# ADC_Temp.net
KiCad netlist of a schematic drawn in Altium Designer
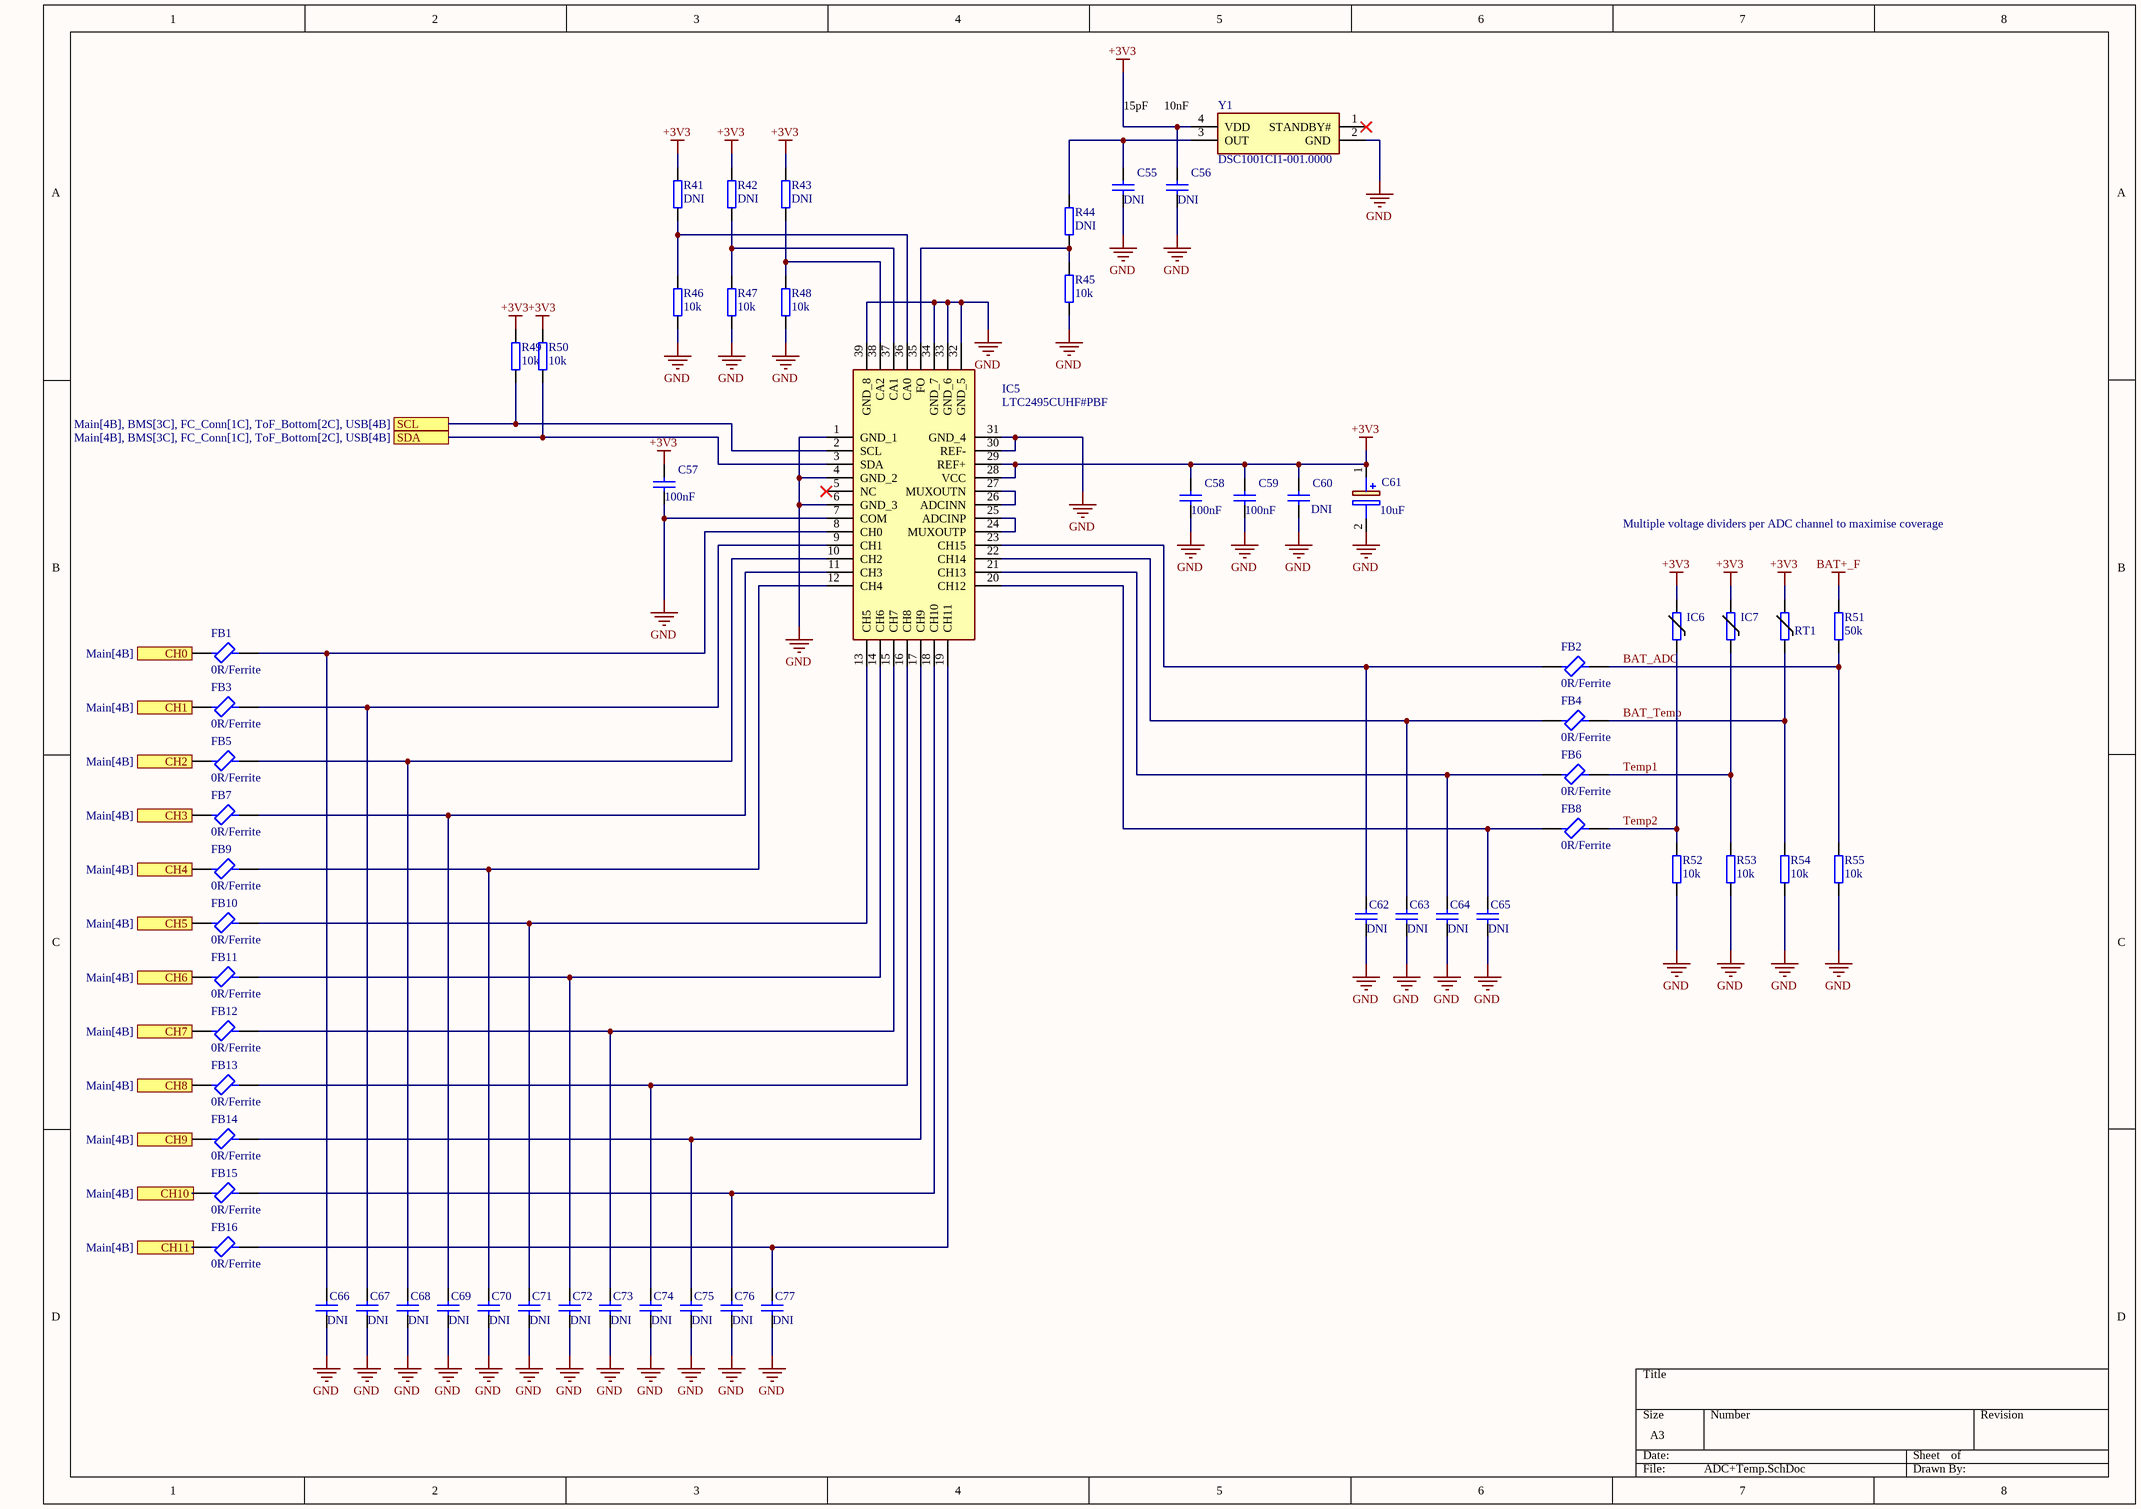
[diagram p0: ADC+Temp.SchDoc]

(export (version "E")
  (design (tool "Eeschema 10.0.6"))
  (components
    (comp (ref "C55")
      (value "DNI")
      (footprint "CAP0402")
      (fields (field (name "Comment") "Cap0402"))
      (libsource (lib "capacitorsSMD") (part "Cap0402"))
    )
    (comp (ref "C56")
      (value "DNI")
      (footprint "CAP0402")
      (fields (field (name "Comment") "Cap0402"))
      (libsource (lib "capacitorsSMD") (part "Cap0402"))
    )
    (comp (ref "C57")
      (value "100nF")
      (footprint "CAP0402")
      (fields (field (name "VOLTAGE") "50V") (field (name "Comment") "Cap0402"))
      (libsource (lib "capacitorsSMD") (part "Cap0402"))
    )
    (comp (ref "C58")
      (value "100nF")
      (footprint "CAP0402")
      (fields (field (name "VOLTAGE") "50V") (field (name "Comment") "Cap0402"))
      (libsource (lib "capacitorsSMD") (part "Cap0402"))
    )
    (comp (ref "C59")
      (value "100nF")
      (footprint "CAP0402")
      (fields (field (name "VOLTAGE") "50V") (field (name "Comment") "Cap0402"))
      (libsource (lib "capacitorsSMD") (part "Cap0402"))
    )
    (comp (ref "C60")
      (value "DNI")
      (footprint "CAP0603")
      (fields (field (name "Comment") "Cap0603"))
      (libsource (lib "capacitorsSMD") (part "Cap0603"))
    )
    (comp (ref "C61")
      (value "10uF")
      (footprint "SamacSys:CAPPC1608X90N")
      (description "Capacitor Polarised")
      (fields (field (name "VOLTAGE") "6V3") (field (name "Comment") "TMCJ0J106MTRF"))
      (libsource (lib "*") (part "298D106X96R3M2T"))
    )
    (comp (ref "C62")
      (value "DNI")
      (footprint "CAP0402")
      (fields (field (name "Comment") "Cap0402"))
      (libsource (lib "capacitorsSMD") (part "Cap0402"))
    )
    (comp (ref "C63")
      (value "DNI")
      (footprint "CAP0402")
      (fields (field (name "Comment") "Cap0402"))
      (libsource (lib "capacitorsSMD") (part "Cap0402"))
    )
    (comp (ref "C64")
      (value "DNI")
      (footprint "CAP0402")
      (fields (field (name "Comment") "Cap0402"))
      (libsource (lib "capacitorsSMD") (part "Cap0402"))
    )
    (comp (ref "C65")
      (value "DNI")
      (footprint "CAP0402")
      (fields (field (name "Comment") "Cap0402"))
      (libsource (lib "capacitorsSMD") (part "Cap0402"))
    )
    (comp (ref "C66")
      (value "DNI")
      (footprint "CAP0402")
      (fields (field (name "Comment") "Cap0402"))
      (libsource (lib "capacitorsSMD") (part "Cap0402"))
    )
    (comp (ref "C67")
      (value "DNI")
      (footprint "CAP0402")
      (fields (field (name "Comment") "Cap0402"))
      (libsource (lib "capacitorsSMD") (part "Cap0402"))
    )
    (comp (ref "C68")
      (value "DNI")
      (footprint "CAP0402")
      (fields (field (name "Comment") "Cap0402"))
      (libsource (lib "capacitorsSMD") (part "Cap0402"))
    )
    (comp (ref "C69")
      (value "DNI")
      (footprint "CAP0402")
      (fields (field (name "Comment") "Cap0402"))
      (libsource (lib "capacitorsSMD") (part "Cap0402"))
    )
    (comp (ref "C70")
      (value "DNI")
      (footprint "CAP0402")
      (fields (field (name "Comment") "Cap0402"))
      (libsource (lib "capacitorsSMD") (part "Cap0402"))
    )
    (comp (ref "C71")
      (value "DNI")
      (footprint "CAP0402")
      (fields (field (name "Comment") "Cap0402"))
      (libsource (lib "capacitorsSMD") (part "Cap0402"))
    )
    (comp (ref "C72")
      (value "DNI")
      (footprint "CAP0402")
      (fields (field (name "Comment") "Cap0402"))
      (libsource (lib "capacitorsSMD") (part "Cap0402"))
    )
    (comp (ref "C73")
      (value "DNI")
      (footprint "CAP0402")
      (fields (field (name "Comment") "Cap0402"))
      (libsource (lib "capacitorsSMD") (part "Cap0402"))
    )
    (comp (ref "C74")
      (value "DNI")
      (footprint "CAP0402")
      (fields (field (name "Comment") "Cap0402"))
      (libsource (lib "capacitorsSMD") (part "Cap0402"))
    )
    (comp (ref "C75")
      (value "DNI")
      (footprint "CAP0402")
      (fields (field (name "Comment") "Cap0402"))
      (libsource (lib "capacitorsSMD") (part "Cap0402"))
    )
    (comp (ref "C76")
      (value "DNI")
      (footprint "CAP0402")
      (fields (field (name "Comment") "Cap0402"))
      (libsource (lib "capacitorsSMD") (part "Cap0402"))
    )
    (comp (ref "C77")
      (value "DNI")
      (footprint "CAP0402")
      (fields (field (name "Comment") "Cap0402"))
      (libsource (lib "capacitorsSMD") (part "Cap0402"))
    )
    (comp (ref "FB1")
      (value "0R/Ferrite")
      (footprint "SamacSys:NFZ15SG152SN10B")
      (description "Ferrite Bead")
      (fields
        (field (name "MANUFACTURER_PART_NUMBER") "BLM15PE471SH1D")
        (field (name "MOUSER PART NUMBER") "81-BLM15PE471SH1D")
      )
      (libsource (lib "SamacSys") (part "BLM15PE471SH1D"))
    )
    (comp (ref "FB2")
      (value "0R/Ferrite")
      (footprint "SamacSys:NFZ15SG152SN10B")
      (description "Ferrite Bead")
      (fields
        (field (name "MANUFACTURER_PART_NUMBER") "BLM15PE471SH1D")
        (field (name "MOUSER PART NUMBER") "81-BLM15PE471SH1D")
      )
      (libsource (lib "SamacSys") (part "BLM15PE471SH1D"))
    )
    (comp (ref "FB3")
      (value "0R/Ferrite")
      (footprint "SamacSys:NFZ15SG152SN10B")
      (description "Ferrite Bead")
      (fields
        (field (name "MANUFACTURER_PART_NUMBER") "BLM15PE471SH1D")
        (field (name "MOUSER PART NUMBER") "81-BLM15PE471SH1D")
      )
      (libsource (lib "SamacSys") (part "BLM15PE471SH1D"))
    )
    (comp (ref "FB4")
      (value "0R/Ferrite")
      (footprint "SamacSys:NFZ15SG152SN10B")
      (description "Ferrite Bead")
      (fields
        (field (name "MANUFACTURER_PART_NUMBER") "BLM15PE471SH1D")
        (field (name "MOUSER PART NUMBER") "81-BLM15PE471SH1D")
      )
      (libsource (lib "SamacSys") (part "BLM15PE471SH1D"))
    )
    (comp (ref "FB5")
      (value "0R/Ferrite")
      (footprint "SamacSys:NFZ15SG152SN10B")
      (description "Ferrite Bead")
      (fields
        (field (name "MANUFACTURER_PART_NUMBER") "BLM15PE471SH1D")
        (field (name "MOUSER PART NUMBER") "81-BLM15PE471SH1D")
      )
      (libsource (lib "SamacSys") (part "BLM15PE471SH1D"))
    )
    (comp (ref "FB6")
      (value "0R/Ferrite")
      (footprint "SamacSys:NFZ15SG152SN10B")
      (description "Ferrite Bead")
      (fields
        (field (name "MANUFACTURER_PART_NUMBER") "BLM15PE471SH1D")
        (field (name "MOUSER PART NUMBER") "81-BLM15PE471SH1D")
      )
      (libsource (lib "SamacSys") (part "BLM15PE471SH1D"))
    )
    (comp (ref "FB7")
      (value "0R/Ferrite")
      (footprint "SamacSys:NFZ15SG152SN10B")
      (description "Ferrite Bead")
      (fields
        (field (name "MANUFACTURER_PART_NUMBER") "BLM15PE471SH1D")
        (field (name "MOUSER PART NUMBER") "81-BLM15PE471SH1D")
      )
      (libsource (lib "SamacSys") (part "BLM15PE471SH1D"))
    )
    (comp (ref "FB8")
      (value "0R/Ferrite")
      (footprint "SamacSys:NFZ15SG152SN10B")
      (description "Ferrite Bead")
      (fields
        (field (name "MANUFACTURER_PART_NUMBER") "BLM15PE471SH1D")
        (field (name "MOUSER PART NUMBER") "81-BLM15PE471SH1D")
      )
      (libsource (lib "SamacSys") (part "BLM15PE471SH1D"))
    )
    (comp (ref "FB9")
      (value "0R/Ferrite")
      (footprint "SamacSys:NFZ15SG152SN10B")
      (description "Ferrite Bead")
      (fields
        (field (name "MANUFACTURER_PART_NUMBER") "BLM15PE471SH1D")
        (field (name "MOUSER PART NUMBER") "81-BLM15PE471SH1D")
      )
      (libsource (lib "SamacSys") (part "BLM15PE471SH1D"))
    )
    (comp (ref "FB10")
      (value "0R/Ferrite")
      (footprint "SamacSys:NFZ15SG152SN10B")
      (description "Ferrite Bead")
      (fields
        (field (name "MANUFACTURER_PART_NUMBER") "BLM15PE471SH1D")
        (field (name "MOUSER PART NUMBER") "81-BLM15PE471SH1D")
      )
      (libsource (lib "SamacSys") (part "BLM15PE471SH1D"))
    )
    (comp (ref "FB11")
      (value "0R/Ferrite")
      (footprint "SamacSys:NFZ15SG152SN10B")
      (description "Ferrite Bead")
      (fields
        (field (name "MANUFACTURER_PART_NUMBER") "BLM15PE471SH1D")
        (field (name "MOUSER PART NUMBER") "81-BLM15PE471SH1D")
      )
      (libsource (lib "SamacSys") (part "BLM15PE471SH1D"))
    )
    (comp (ref "FB12")
      (value "0R/Ferrite")
      (footprint "SamacSys:NFZ15SG152SN10B")
      (description "Ferrite Bead")
      (fields
        (field (name "MANUFACTURER_PART_NUMBER") "BLM15PE471SH1D")
        (field (name "MOUSER PART NUMBER") "81-BLM15PE471SH1D")
      )
      (libsource (lib "SamacSys") (part "BLM15PE471SH1D"))
    )
    (comp (ref "FB13")
      (value "0R/Ferrite")
      (footprint "SamacSys:NFZ15SG152SN10B")
      (description "Ferrite Bead")
      (fields
        (field (name "MANUFACTURER_PART_NUMBER") "BLM15PE471SH1D")
        (field (name "MOUSER PART NUMBER") "81-BLM15PE471SH1D")
      )
      (libsource (lib "SamacSys") (part "BLM15PE471SH1D"))
    )
    (comp (ref "FB14")
      (value "0R/Ferrite")
      (footprint "SamacSys:NFZ15SG152SN10B")
      (description "Ferrite Bead")
      (fields
        (field (name "MANUFACTURER_PART_NUMBER") "BLM15PE471SH1D")
        (field (name "MOUSER PART NUMBER") "81-BLM15PE471SH1D")
      )
      (libsource (lib "SamacSys") (part "BLM15PE471SH1D"))
    )
    (comp (ref "FB15")
      (value "0R/Ferrite")
      (footprint "SamacSys:NFZ15SG152SN10B")
      (description "Ferrite Bead")
      (fields
        (field (name "MANUFACTURER_PART_NUMBER") "BLM15PE471SH1D")
        (field (name "MOUSER PART NUMBER") "81-BLM15PE471SH1D")
      )
      (libsource (lib "SamacSys") (part "BLM15PE471SH1D"))
    )
    (comp (ref "FB16")
      (value "0R/Ferrite")
      (footprint "SamacSys:NFZ15SG152SN10B")
      (description "Ferrite Bead")
      (fields
        (field (name "MANUFACTURER_PART_NUMBER") "BLM15PE471SH1D")
        (field (name "MOUSER PART NUMBER") "81-BLM15PE471SH1D")
      )
      (libsource (lib "SamacSys") (part "BLM15PE471SH1D"))
    )
    (comp (ref "IC5")
      (value "LTC2495CUHF#PBF")
      (footprint "SamacSys:QFN50P500X700X80-39N-D")
      (description "Integrated Circuit")
      (fields (field (name "MOUSER PART NUMBER") "584-LTC2495CUHF#PBF"))
      (libsource (lib "*") (part "LTC2495CUHF#PBF"))
    )
    (comp (ref "IC6")
      (value "TMP6131DECR")
      (footprint "SamacSys:TMP6131DECR")
      (description "Integrated Circuit")
      (fields (field (name "MOUSER PART NUMBER") "595-TMP6131DECR"))
      (libsource (lib "SamacSys") (part "TMP6131DECR"))
    )
    (comp (ref "IC7")
      (value "TMP6131DECR")
      (footprint "SamacSys:TMP6131DECR")
      (description "Integrated Circuit")
      (fields (field (name "MOUSER PART NUMBER") "595-TMP6131DECR"))
      (libsource (lib "SamacSys") (part "TMP6131DECR"))
    )
    (comp (ref "R41")
      (value "DNI")
      (footprint "RES0402")
      (fields (field (name "Comment") "Res0402"))
      (libsource (lib "resistorSMD") (part "Res0402"))
    )
    (comp (ref "R42")
      (value "DNI")
      (footprint "RES0402")
      (fields (field (name "Comment") "Res0402"))
      (libsource (lib "resistorSMD") (part "Res0402"))
    )
    (comp (ref "R43")
      (value "DNI")
      (footprint "RES0402")
      (fields (field (name "Comment") "Res0402"))
      (libsource (lib "resistorSMD") (part "Res0402"))
    )
    (comp (ref "R44")
      (value "DNI")
      (footprint "RES0402")
      (fields (field (name "Comment") "Res0402"))
      (libsource (lib "resistorSMD") (part "Res0402"))
    )
    (comp (ref "R45")
      (value "10k")
      (footprint "RES0402")
      (fields (field (name "Comment") "Res0402"))
      (libsource (lib "resistorSMD") (part "Res0402"))
    )
    (comp (ref "R46")
      (value "10k")
      (footprint "RES0402")
      (fields (field (name "Comment") "Res0402"))
      (libsource (lib "resistorSMD") (part "Res0402"))
    )
    (comp (ref "R47")
      (value "10k")
      (footprint "RES0402")
      (fields (field (name "Comment") "Res0402"))
      (libsource (lib "resistorSMD") (part "Res0402"))
    )
    (comp (ref "R48")
      (value "10k")
      (footprint "RES0402")
      (fields (field (name "Comment") "Res0402"))
      (libsource (lib "resistorSMD") (part "Res0402"))
    )
    (comp (ref "R49")
      (value "10k")
      (footprint "RES0402")
      (fields (field (name "Comment") "Res0402"))
      (libsource (lib "resistorSMD") (part "Res0402"))
    )
    (comp (ref "R50")
      (value "10k")
      (footprint "RES0402")
      (fields (field (name "Comment") "Res0402"))
      (libsource (lib "resistorSMD") (part "Res0402"))
    )
    (comp (ref "R51")
      (value "50k")
      (footprint "RES0402")
      (fields (field (name "Comment") "Res0402"))
      (libsource (lib "resistorSMD") (part "Res0402"))
    )
    (comp (ref "R52")
      (value "10k")
      (footprint "RES0402")
      (fields (field (name "Comment") "Res0402"))
      (libsource (lib "resistorSMD") (part "Res0402"))
    )
    (comp (ref "R53")
      (value "10k")
      (footprint "RES0402")
      (fields (field (name "Comment") "Res0402"))
      (libsource (lib "resistorSMD") (part "Res0402"))
    )
    (comp (ref "R54")
      (value "10k")
      (footprint "RES0402")
      (fields (field (name "Comment") "Res0402"))
      (libsource (lib "resistorSMD") (part "Res0402"))
    )
    (comp (ref "R55")
      (value "10k")
      (footprint "RES0402")
      (fields (field (name "Comment") "Res0402"))
      (libsource (lib "resistorSMD") (part "Res0402"))
    )
    (comp (ref "RT1")
      (value "B57862L0103F000/B59100M1080A070")
      (footprint "SamacSys:B57862L0102F000")
      (description "Thermistor")
      (fields
        (field (name "MANUFACTURER_PART_NUMBER") "B57862L0103F000")
        (field (name "MOUSER PART NUMBER") "871-B57862L0103F000")
      )
      (libsource (lib "SamacSys") (part "B57862L0103F000"))
    )
    (comp (ref "Y1")
      (value "DSC1001CI1-001.0000")
      (footprint "SamacSys:DSC1001CI10010000")
      (description "DNI")
      (fields (field (name "MOUSER PART NUMBER") "998-1001CI1-001.0000"))
      (libsource (lib "*") (part "DSC1001CI1-001.0000"))
    )
  )
  (nets
    (net (code "1") (name "+3V3") (class "Default")
      (node (ref "C56") (pin "2") (pinfunction "2_2") (pintype "passive"))
      (node (ref "C57") (pin "2") (pinfunction "2_2") (pintype "passive"))
      (node (ref "C58") (pin "2") (pinfunction "2_2") (pintype "passive"))
      (node (ref "C59") (pin "2") (pinfunction "2_2") (pintype "passive"))
      (node (ref "C60") (pin "2") (pinfunction "2_2") (pintype "passive"))
      (node (ref "C61") (pin "1") (pinfunction "+_1") (pintype "passive"))
      (node (ref "IC5") (pin "28") (pinfunction "VCC_28") (pintype "passive"))
      (node (ref "IC5") (pin "29") (pinfunction "REF+_29") (pintype "passive"))
      (node (ref "IC6") (pin "2") (pinfunction "2_2") (pintype "passive"))
      (node (ref "IC7") (pin "2") (pinfunction "2_2") (pintype "passive"))
      (node (ref "R41") (pin "2") (pinfunction "2_2") (pintype "passive"))
      (node (ref "R42") (pin "2") (pinfunction "2_2") (pintype "passive"))
      (node (ref "R43") (pin "2") (pinfunction "2_2") (pintype "passive"))
      (node (ref "R49") (pin "2") (pinfunction "2_2") (pintype "passive"))
      (node (ref "R50") (pin "2") (pinfunction "2_2") (pintype "passive"))
      (node (ref "RT1") (pin "2") (pinfunction "2_2") (pintype "passive"))
      (node (ref "Y1") (pin "4") (pinfunction "VDD_4") (pintype "passive"))
    )
    (net (code "2") (name "/BAT_ADC") (class "Default")
      (node (ref "FB2") (pin "2") (pinfunction "2_2") (pintype "passive"))
      (node (ref "R51") (pin "1") (pinfunction "1_1") (pintype "passive"))
      (node (ref "R55") (pin "2") (pinfunction "2_2") (pintype "passive"))
    )
    (net (code "3") (name "/BAT_Temp") (class "Default")
      (node (ref "FB4") (pin "2") (pinfunction "2_2") (pintype "passive"))
      (node (ref "R54") (pin "2") (pinfunction "2_2") (pintype "passive"))
      (node (ref "RT1") (pin "1") (pinfunction "1_1") (pintype "passive"))
    )
    (net (code "4") (name "/CH0") (class "Default")
      (node (ref "FB1") (pin "1") (pinfunction "1_1") (pintype "passive"))
    )
    (net (code "5") (name "/CH1") (class "Default")
      (node (ref "FB3") (pin "1") (pinfunction "1_1") (pintype "passive"))
    )
    (net (code "6") (name "/CH2") (class "Default")
      (node (ref "FB5") (pin "1") (pinfunction "1_1") (pintype "passive"))
    )
    (net (code "7") (name "/CH3") (class "Default")
      (node (ref "FB7") (pin "1") (pinfunction "1_1") (pintype "passive"))
    )
    (net (code "8") (name "/CH4") (class "Default")
      (node (ref "FB9") (pin "1") (pinfunction "1_1") (pintype "passive"))
    )
    (net (code "9") (name "/CH5") (class "Default")
      (node (ref "FB10") (pin "1") (pinfunction "1_1") (pintype "passive"))
    )
    (net (code "10") (name "/CH6") (class "Default")
      (node (ref "FB11") (pin "1") (pinfunction "1_1") (pintype "passive"))
    )
    (net (code "11") (name "/CH7") (class "Default")
      (node (ref "FB12") (pin "1") (pinfunction "1_1") (pintype "passive"))
    )
    (net (code "12") (name "/CH8") (class "Default")
      (node (ref "FB13") (pin "1") (pinfunction "1_1") (pintype "passive"))
    )
    (net (code "13") (name "/CH9") (class "Default")
      (node (ref "FB14") (pin "1") (pinfunction "1_1") (pintype "passive"))
    )
    (net (code "14") (name "/CH10") (class "Default")
      (node (ref "FB15") (pin "1") (pinfunction "1_1") (pintype "passive"))
    )
    (net (code "15") (name "/CH11") (class "Default")
      (node (ref "FB16") (pin "1") (pinfunction "1_1") (pintype "passive"))
    )
    (net (code "16") (name "/SCL") (class "Default")
      (node (ref "IC5") (pin "2") (pinfunction "SCL_2") (pintype "passive"))
      (node (ref "R49") (pin "1") (pinfunction "1_1") (pintype "passive"))
    )
    (net (code "17") (name "/SDA") (class "Default")
      (node (ref "IC5") (pin "3") (pinfunction "SDA_3") (pintype "passive"))
      (node (ref "R50") (pin "1") (pinfunction "1_1") (pintype "passive"))
    )
    (net (code "18") (name "/Temp1") (class "Default")
      (node (ref "FB6") (pin "2") (pinfunction "2_2") (pintype "passive"))
      (node (ref "IC7") (pin "1") (pinfunction "1_1") (pintype "passive"))
      (node (ref "R53") (pin "2") (pinfunction "2_2") (pintype "passive"))
    )
    (net (code "19") (name "/Temp2") (class "Default")
      (node (ref "FB8") (pin "2") (pinfunction "2_2") (pintype "passive"))
      (node (ref "IC6") (pin "1") (pinfunction "1_1") (pintype "passive"))
      (node (ref "R52") (pin "2") (pinfunction "2_2") (pintype "passive"))
    )
    (net (code "20") (name "BAT+_F") (class "Default")
      (node (ref "R51") (pin "2") (pinfunction "2_2") (pintype "passive"))
    )
    (net (code "21") (name "GND") (class "Default")
      (node (ref "C55") (pin "1") (pinfunction "1_1") (pintype "passive"))
      (node (ref "C56") (pin "1") (pinfunction "1_1") (pintype "passive"))
      (node (ref "C57") (pin "1") (pinfunction "1_1") (pintype "passive"))
      (node (ref "C58") (pin "1") (pinfunction "1_1") (pintype "passive"))
      (node (ref "C59") (pin "1") (pinfunction "1_1") (pintype "passive"))
      (node (ref "C60") (pin "1") (pinfunction "1_1") (pintype "passive"))
      (node (ref "C61") (pin "2") (pinfunction "-_2") (pintype "passive"))
      (node (ref "C62") (pin "1") (pinfunction "1_1") (pintype "passive"))
      (node (ref "C63") (pin "1") (pinfunction "1_1") (pintype "passive"))
      (node (ref "C64") (pin "1") (pinfunction "1_1") (pintype "passive"))
      (node (ref "C65") (pin "1") (pinfunction "1_1") (pintype "passive"))
      (node (ref "C66") (pin "1") (pinfunction "1_1") (pintype "passive"))
      (node (ref "C67") (pin "1") (pinfunction "1_1") (pintype "passive"))
      (node (ref "C68") (pin "1") (pinfunction "1_1") (pintype "passive"))
      (node (ref "C69") (pin "1") (pinfunction "1_1") (pintype "passive"))
      (node (ref "C70") (pin "1") (pinfunction "1_1") (pintype "passive"))
      (node (ref "C71") (pin "1") (pinfunction "1_1") (pintype "passive"))
      (node (ref "C72") (pin "1") (pinfunction "1_1") (pintype "passive"))
      (node (ref "C73") (pin "1") (pinfunction "1_1") (pintype "passive"))
      (node (ref "C74") (pin "1") (pinfunction "1_1") (pintype "passive"))
      (node (ref "C75") (pin "1") (pinfunction "1_1") (pintype "passive"))
      (node (ref "C76") (pin "1") (pinfunction "1_1") (pintype "passive"))
      (node (ref "C77") (pin "1") (pinfunction "1_1") (pintype "passive"))
      (node (ref "IC5") (pin "1") (pinfunction "GND_1_1") (pintype "passive"))
      (node (ref "IC5") (pin "30") (pinfunction "REF-_30") (pintype "passive"))
      (node (ref "IC5") (pin "31") (pinfunction "GND_4_31") (pintype "passive"))
      (node (ref "IC5") (pin "32") (pinfunction "GND_5_32") (pintype "passive"))
      (node (ref "IC5") (pin "33") (pinfunction "GND_6_33") (pintype "passive"))
      (node (ref "IC5") (pin "34") (pinfunction "GND_7_34") (pintype "passive"))
      (node (ref "IC5") (pin "39") (pinfunction "GND_8_39") (pintype "passive"))
      (node (ref "IC5") (pin "4") (pinfunction "GND_2_4") (pintype "passive"))
      (node (ref "IC5") (pin "6") (pinfunction "GND_3_6") (pintype "passive"))
      (node (ref "IC5") (pin "7") (pinfunction "COM_7") (pintype "passive"))
      (node (ref "R45") (pin "1") (pinfunction "1_1") (pintype "passive"))
      (node (ref "R46") (pin "1") (pinfunction "1_1") (pintype "passive"))
      (node (ref "R47") (pin "1") (pinfunction "1_1") (pintype "passive"))
      (node (ref "R48") (pin "1") (pinfunction "1_1") (pintype "passive"))
      (node (ref "R52") (pin "1") (pinfunction "1_1") (pintype "passive"))
      (node (ref "R53") (pin "1") (pinfunction "1_1") (pintype "passive"))
      (node (ref "R54") (pin "1") (pinfunction "1_1") (pintype "passive"))
      (node (ref "R55") (pin "1") (pinfunction "1_1") (pintype "passive"))
      (node (ref "Y1") (pin "2") (pinfunction "GND_2") (pintype "passive"))
    )
    (net (code "22") (name "Net-(IC5-ADCINN)") (class "Default")
      (node (ref "IC5") (pin "26") (pinfunction "ADCINN_26") (pintype "passive"))
      (node (ref "IC5") (pin "27") (pinfunction "MUXOUTN_27") (pintype "passive"))
    )
    (net (code "23") (name "Net-(IC5-ADCINP)") (class "Default")
      (node (ref "IC5") (pin "24") (pinfunction "MUXOUTP_24") (pintype "passive"))
      (node (ref "IC5") (pin "25") (pinfunction "ADCINP_25") (pintype "passive"))
    )
    (net (code "24") (name "Net-(IC5-CA0)") (class "Default")
      (node (ref "IC5") (pin "36") (pinfunction "CA0_36") (pintype "passive"))
      (node (ref "R41") (pin "1") (pinfunction "1_1") (pintype "passive"))
      (node (ref "R46") (pin "2") (pinfunction "2_2") (pintype "passive"))
    )
    (net (code "25") (name "Net-(IC5-CA1)") (class "Default")
      (node (ref "IC5") (pin "37") (pinfunction "CA1_37") (pintype "passive"))
      (node (ref "R42") (pin "1") (pinfunction "1_1") (pintype "passive"))
      (node (ref "R47") (pin "2") (pinfunction "2_2") (pintype "passive"))
    )
    (net (code "26") (name "Net-(IC5-CA2)") (class "Default")
      (node (ref "IC5") (pin "38") (pinfunction "CA2_38") (pintype "passive"))
      (node (ref "R43") (pin "1") (pinfunction "1_1") (pintype "passive"))
      (node (ref "R48") (pin "2") (pinfunction "2_2") (pintype "passive"))
    )
    (net (code "27") (name "Net-(IC5-CH0)") (class "Default")
      (node (ref "C66") (pin "2") (pinfunction "2_2") (pintype "passive"))
      (node (ref "FB1") (pin "2") (pinfunction "2_2") (pintype "passive"))
      (node (ref "IC5") (pin "8") (pinfunction "CH0_8") (pintype "passive"))
    )
    (net (code "28") (name "Net-(IC5-CH1)") (class "Default")
      (node (ref "C67") (pin "2") (pinfunction "2_2") (pintype "passive"))
      (node (ref "FB3") (pin "2") (pinfunction "2_2") (pintype "passive"))
      (node (ref "IC5") (pin "9") (pinfunction "CH1_9") (pintype "passive"))
    )
    (net (code "29") (name "Net-(IC5-CH2)") (class "Default")
      (node (ref "C68") (pin "2") (pinfunction "2_2") (pintype "passive"))
      (node (ref "FB5") (pin "2") (pinfunction "2_2") (pintype "passive"))
      (node (ref "IC5") (pin "10") (pinfunction "CH2_10") (pintype "passive"))
    )
    (net (code "30") (name "Net-(IC5-CH3)") (class "Default")
      (node (ref "C69") (pin "2") (pinfunction "2_2") (pintype "passive"))
      (node (ref "FB7") (pin "2") (pinfunction "2_2") (pintype "passive"))
      (node (ref "IC5") (pin "11") (pinfunction "CH3_11") (pintype "passive"))
    )
    (net (code "31") (name "Net-(IC5-CH4)") (class "Default")
      (node (ref "C70") (pin "2") (pinfunction "2_2") (pintype "passive"))
      (node (ref "FB9") (pin "2") (pinfunction "2_2") (pintype "passive"))
      (node (ref "IC5") (pin "12") (pinfunction "CH4_12") (pintype "passive"))
    )
    (net (code "32") (name "Net-(IC5-CH5)") (class "Default")
      (node (ref "C71") (pin "2") (pinfunction "2_2") (pintype "passive"))
      (node (ref "FB10") (pin "2") (pinfunction "2_2") (pintype "passive"))
      (node (ref "IC5") (pin "13") (pinfunction "CH5_13") (pintype "passive"))
    )
    (net (code "33") (name "Net-(IC5-CH6)") (class "Default")
      (node (ref "C72") (pin "2") (pinfunction "2_2") (pintype "passive"))
      (node (ref "FB11") (pin "2") (pinfunction "2_2") (pintype "passive"))
      (node (ref "IC5") (pin "14") (pinfunction "CH6_14") (pintype "passive"))
    )
    (net (code "34") (name "Net-(IC5-CH7)") (class "Default")
      (node (ref "C73") (pin "2") (pinfunction "2_2") (pintype "passive"))
      (node (ref "FB12") (pin "2") (pinfunction "2_2") (pintype "passive"))
      (node (ref "IC5") (pin "15") (pinfunction "CH7_15") (pintype "passive"))
    )
    (net (code "35") (name "Net-(IC5-CH8)") (class "Default")
      (node (ref "C74") (pin "2") (pinfunction "2_2") (pintype "passive"))
      (node (ref "FB13") (pin "2") (pinfunction "2_2") (pintype "passive"))
      (node (ref "IC5") (pin "16") (pinfunction "CH8_16") (pintype "passive"))
    )
    (net (code "36") (name "Net-(IC5-CH9)") (class "Default")
      (node (ref "C75") (pin "2") (pinfunction "2_2") (pintype "passive"))
      (node (ref "FB14") (pin "2") (pinfunction "2_2") (pintype "passive"))
      (node (ref "IC5") (pin "17") (pinfunction "CH9_17") (pintype "passive"))
    )
    (net (code "37") (name "Net-(IC5-CH10)") (class "Default")
      (node (ref "C76") (pin "2") (pinfunction "2_2") (pintype "passive"))
      (node (ref "FB15") (pin "2") (pinfunction "2_2") (pintype "passive"))
      (node (ref "IC5") (pin "18") (pinfunction "CH10_18") (pintype "passive"))
    )
    (net (code "38") (name "Net-(IC5-CH11)") (class "Default")
      (node (ref "C77") (pin "2") (pinfunction "2_2") (pintype "passive"))
      (node (ref "FB16") (pin "2") (pinfunction "2_2") (pintype "passive"))
      (node (ref "IC5") (pin "19") (pinfunction "CH11_19") (pintype "passive"))
    )
    (net (code "39") (name "Net-(IC5-CH12)") (class "Default")
      (node (ref "C65") (pin "2") (pinfunction "2_2") (pintype "passive"))
      (node (ref "FB8") (pin "1") (pinfunction "1_1") (pintype "passive"))
      (node (ref "IC5") (pin "20") (pinfunction "CH12_20") (pintype "passive"))
    )
    (net (code "40") (name "Net-(IC5-CH13)") (class "Default")
      (node (ref "C64") (pin "2") (pinfunction "2_2") (pintype "passive"))
      (node (ref "FB6") (pin "1") (pinfunction "1_1") (pintype "passive"))
      (node (ref "IC5") (pin "21") (pinfunction "CH13_21") (pintype "passive"))
    )
    (net (code "41") (name "Net-(IC5-CH14)") (class "Default")
      (node (ref "C63") (pin "2") (pinfunction "2_2") (pintype "passive"))
      (node (ref "FB4") (pin "1") (pinfunction "1_1") (pintype "passive"))
      (node (ref "IC5") (pin "22") (pinfunction "CH14_22") (pintype "passive"))
    )
    (net (code "42") (name "Net-(IC5-CH15)") (class "Default")
      (node (ref "C62") (pin "2") (pinfunction "2_2") (pintype "passive"))
      (node (ref "FB2") (pin "1") (pinfunction "1_1") (pintype "passive"))
      (node (ref "IC5") (pin "23") (pinfunction "CH15_23") (pintype "passive"))
    )
    (net (code "43") (name "Net-(IC5-FO)") (class "Default")
      (node (ref "IC5") (pin "35") (pinfunction "FO_35") (pintype "passive"))
      (node (ref "R44") (pin "1") (pinfunction "1_1") (pintype "passive"))
      (node (ref "R45") (pin "2") (pinfunction "2_2") (pintype "passive"))
    )
    (net (code "44") (name "Net-(Y1-OUT)") (class "Default")
      (node (ref "C55") (pin "2") (pinfunction "2_2") (pintype "passive"))
      (node (ref "R44") (pin "2") (pinfunction "2_2") (pintype "passive"))
      (node (ref "Y1") (pin "3") (pinfunction "OUT_3") (pintype "passive"))
    )
    (net (code "45") (name "unconnected-(IC5-NC-Pad5)") (class "Default")
      (node (ref "IC5") (pin "5") (pinfunction "NC_5") (pintype "passive+no_connect"))
    )
    (net (code "46") (name "unconnected-(Y1-STANDBY#-Pad1)") (class "Default")
      (node (ref "Y1") (pin "1") (pinfunction "STANDBY#_1") (pintype "passive+no_connect"))
    )
  )
)
